# Wireless.net
KiCad netlist of a schematic drawn in Altium Designer
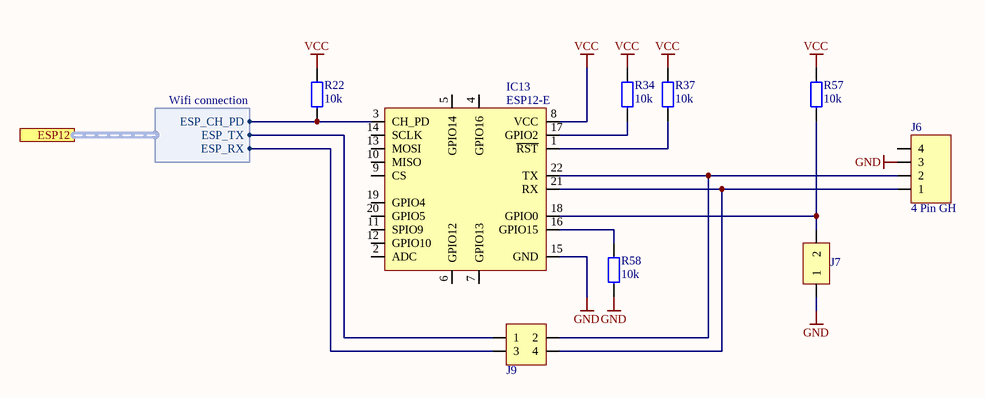
[diagram p0: Wireless.SchDoc]

(export (version "E")
  (design (tool "Eeschema 10.0.6"))
  (components
    (comp (ref "IC13")
      (value "ESP12-E")
      (footprint "ESP8266 ESP-12-E")
      (description "Wifi module, esp12-e, based on ESP8266 chip")
      (libsource (lib "uC") (part "ESP-12E"))
    )
    (comp (ref "J6")
      (value "4 Pin GH")
      (footprint "BM04B")
      (description "Złącze GH, męskie, proste, 4 piny, SMD")
      (libsource (lib "Connectors") (part "4 Pin GH"))
    )
    (comp (ref "J7")
      (value "2 pin")
      (footprint "Harwin vertical smt header - single")
      (description "2 pin vertical connection smt harvin")
      (libsource (lib "Connectors") (part "harvin vertical smt header - single"))
    )
    (comp (ref "J9")
      (value "4 pin")
      (footprint "Harwin vertical smt header - double")
      (description "4 pin vertical connection smt harvin")
      (libsource (lib "Connectors") (part "harvin vertical smt header - double"))
    )
    (comp (ref "R22")
      (value "10k")
      (footprint "RES 0603")
      (description "SMDResistor")
      (libsource (lib "Passive") (part "Resistor"))
    )
    (comp (ref "R34")
      (value "10k")
      (footprint "RES 0603")
      (description "SMDResistor")
      (libsource (lib "Passive") (part "Resistor"))
    )
    (comp (ref "R37")
      (value "10k")
      (footprint "RES 0603")
      (description "SMDResistor")
      (libsource (lib "Passive") (part "Resistor"))
    )
    (comp (ref "R57")
      (value "10k")
      (footprint "RES 0603")
      (description "SMDResistor")
      (libsource (lib "Passive") (part "Resistor"))
    )
    (comp (ref "R58")
      (value "10k")
      (footprint "RES 0603")
      (description "SMDResistor")
      (libsource (lib "Passive") (part "Resistor"))
    )
  )
  (nets
    (net (code "3") (name "/ESP_CH_PD") (class "Default")
      (node (ref "IC13") (pin "3") (pinfunction "CH_PD_3") (pintype "passive"))
      (node (ref "R22") (pin "1") (pinfunction "1_1") (pintype "passive"))
    )
    (net (code "4") (name "/ESP_RX") (class "Default")
      (node (ref "J9") (pin "3") (pinfunction "3_3") (pintype "passive"))
    )
    (net (code "5") (name "/ESP_TX") (class "Default")
      (node (ref "J9") (pin "1") (pinfunction "1_1") (pintype "passive"))
    )
    (net (code "7") (name "GND") (class "Default")
      (node (ref "IC13") (pin "15") (pinfunction "GND_15") (pintype "passive"))
      (node (ref "J6") (pin "3") (pinfunction "3_3") (pintype "passive"))
      (node (ref "J7") (pin "1") (pinfunction "1_1") (pintype "passive"))
      (node (ref "R58") (pin "1") (pinfunction "1_1") (pintype "passive"))
    )
    (net (code "8") (name "Net-(IC13-GPIO0)") (class "Default")
      (node (ref "IC13") (pin "18") (pinfunction "GPIO0_18") (pintype "passive"))
      (node (ref "J7") (pin "2") (pinfunction "2_2") (pintype "passive"))
      (node (ref "R57") (pin "1") (pinfunction "1_1") (pintype "passive"))
    )
    (net (code "9") (name "Net-(IC13-GPIO2)") (class "Default")
      (node (ref "IC13") (pin "17") (pinfunction "GPIO2_17") (pintype "passive"))
      (node (ref "R34") (pin "1") (pinfunction "1_1") (pintype "passive"))
    )
    (net (code "10") (name "Net-(IC13-GPIO15)") (class "Default")
      (node (ref "IC13") (pin "16") (pinfunction "GPIO15_16") (pintype "passive"))
      (node (ref "R58") (pin "2") (pinfunction "2_2") (pintype "passive"))
    )
    (net (code "11") (name "Net-(IC13-RX)") (class "Default")
      (node (ref "IC13") (pin "21") (pinfunction "RX_21") (pintype "passive"))
      (node (ref "J6") (pin "1") (pinfunction "1_1") (pintype "passive"))
      (node (ref "J9") (pin "4") (pinfunction "4_4") (pintype "passive"))
    )
    (net (code "12") (name "Net-(IC13-TX)") (class "Default")
      (node (ref "IC13") (pin "22") (pinfunction "TX_22") (pintype "passive"))
      (node (ref "J6") (pin "2") (pinfunction "2_2") (pintype "passive"))
      (node (ref "J9") (pin "2") (pinfunction "2_2") (pintype "passive"))
    )
    (net (code "13") (name "Net-(IC13-~{RST})") (class "Default")
      (node (ref "IC13") (pin "1") (pinfunction "~{RST}_1") (pintype "passive"))
      (node (ref "R37") (pin "1") (pinfunction "1_1") (pintype "passive"))
    )
    (net (code "14") (name "VCC") (class "Default")
      (node (ref "IC13") (pin "8") (pinfunction "VCC_8") (pintype "passive"))
      (node (ref "R22") (pin "2") (pinfunction "2_2") (pintype "passive"))
      (node (ref "R34") (pin "2") (pinfunction "2_2") (pintype "passive"))
      (node (ref "R37") (pin "2") (pinfunction "2_2") (pintype "passive"))
      (node (ref "R57") (pin "2") (pinfunction "2_2") (pintype "passive"))
    )
    (net (code "15") (name "unconnected-(IC13-ADC-Pad2)") (class "Default")
      (node (ref "IC13") (pin "2") (pinfunction "ADC_2") (pintype "passive"))
    )
    (net (code "16") (name "unconnected-(IC13-CS-Pad9)") (class "Default")
      (node (ref "IC13") (pin "9") (pinfunction "CS_9") (pintype "passive"))
    )
    (net (code "17") (name "unconnected-(IC13-GPIO4-Pad19)") (class "Default")
      (node (ref "IC13") (pin "19") (pinfunction "GPIO4_19") (pintype "passive"))
    )
    (net (code "18") (name "unconnected-(IC13-GPIO5-Pad20)") (class "Default")
      (node (ref "IC13") (pin "20") (pinfunction "GPIO5_20") (pintype "passive"))
    )
    (net (code "19") (name "unconnected-(IC13-GPIO10-Pad12)") (class "Default")
      (node (ref "IC13") (pin "12") (pinfunction "GPIO10_12") (pintype "passive"))
    )
    (net (code "20") (name "unconnected-(IC13-GPIO12-Pad6)") (class "Default")
      (node (ref "IC13") (pin "6") (pinfunction "GPIO12_6") (pintype "passive"))
    )
    (net (code "21") (name "unconnected-(IC13-GPIO13-Pad7)") (class "Default")
      (node (ref "IC13") (pin "7") (pinfunction "GPIO13_7") (pintype "passive"))
    )
    (net (code "22") (name "unconnected-(IC13-GPIO14-Pad5)") (class "Default")
      (node (ref "IC13") (pin "5") (pinfunction "GPIO14_5") (pintype "passive"))
    )
    (net (code "23") (name "unconnected-(IC13-GPIO16-Pad4)") (class "Default")
      (node (ref "IC13") (pin "4") (pinfunction "GPIO16_4") (pintype "passive"))
    )
    (net (code "24") (name "unconnected-(IC13-MISO-Pad10)") (class "Default")
      (node (ref "IC13") (pin "10") (pinfunction "MISO_10") (pintype "passive"))
    )
    (net (code "25") (name "unconnected-(IC13-MOSI-Pad13)") (class "Default")
      (node (ref "IC13") (pin "13") (pinfunction "MOSI_13") (pintype "passive"))
    )
    (net (code "26") (name "unconnected-(IC13-SCLK-Pad14)") (class "Default")
      (node (ref "IC13") (pin "14") (pinfunction "SCLK_14") (pintype "passive"))
    )
    (net (code "27") (name "unconnected-(IC13-SPIO9-Pad11)") (class "Default")
      (node (ref "IC13") (pin "11") (pinfunction "SPIO9_11") (pintype "passive"))
    )
    (net (code "28") (name "unconnected-(J6-Pad4)") (class "Default")
      (node (ref "J6") (pin "4") (pinfunction "4_4") (pintype "passive"))
    )
  )
)
